# NUCLEO.net
KiCad netlist of a schematic drawn in Altium Designer
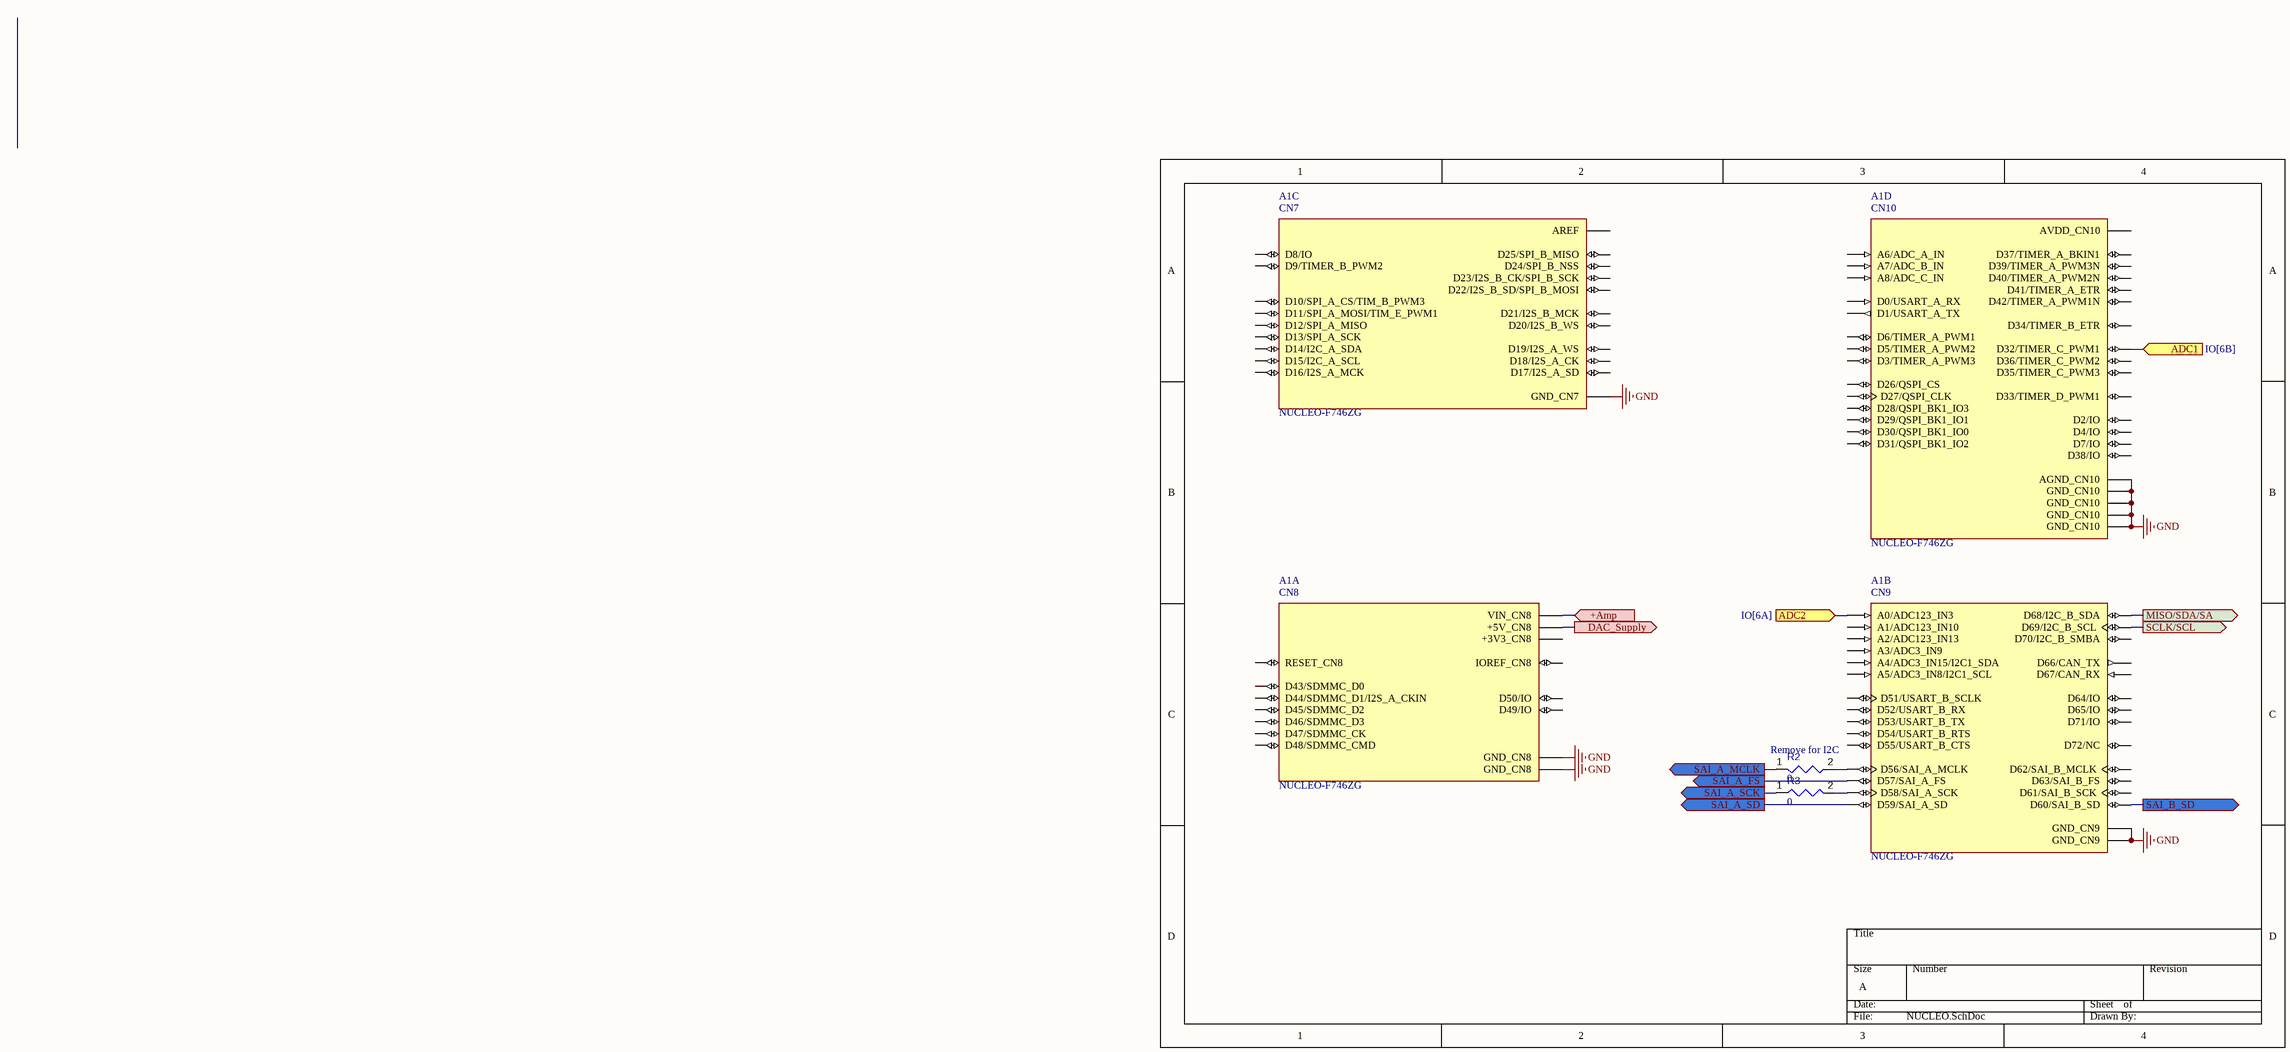
[diagram p0: NUCLEO.SchDoc]

(export (version "E")
  (design (tool "Eeschema 10.0.6"))
  (components
    (comp (ref "A1")
      (value "NUCLEO-F746ZG")
      (footprint "MODULE_NUCLEO-F746ZG")
      (fields (field (name "MF") "STMicroelectronics"))
      (libsource (lib "NUCLEO-F746ZG_NoOutline_InnerRow") (part "NUCLEO-F746ZG"))
    )
    (comp (ref "R2")
      (value "0")
      (footprint "RESC0603(1608)_L")
      (description "0Ohm 0603")
      (libsource (lib "Northeastern University") (part "RES-2"))
    )
    (comp (ref "R3")
      (value "0")
      (footprint "RESC0603(1608)_L")
      (description "0ohm 0603")
      (libsource (lib "Northeastern University") (part "RES-2"))
    )
  )
  (nets
    (net (code "1") (name "/+Amp") (class "Default")
      (node (ref "A1") (pin "CN8_15") (pinfunction "VIN_CN8_CN8_15") (pintype "power_in"))
    )
    (net (code "2") (name "/ADC1") (class "Default")
      (node (ref "A1") (pin "CN10_29") (pinfunction "D32/TIMER_C_PWM1_CN10_29") (pintype "bidirectional"))
    )
    (net (code "3") (name "/ADC2") (class "Default")
      (node (ref "A1") (pin "CN9_1") (pinfunction "A0/ADC123_IN3_CN9_1") (pintype "input"))
    )
    (net (code "4") (name "/DAC_Supply") (class "Default")
      (node (ref "A1") (pin "CN8_9") (pinfunction "+5V_CN8_CN8_9") (pintype "power_in"))
    )
    (net (code "5") (name "/MISO{slash}SDA{slash}SA") (class "Default")
      (node (ref "A1") (pin "CN9_21") (pinfunction "D68/I2C_B_SDA_CN9_21") (pintype "bidirectional"))
    )
    (net (code "6") (name "/SAI_A_FS") (class "Default")
      (node (ref "A1") (pin "CN9_16") (pinfunction "D57/SAI_A_FS_CN9_16") (pintype "bidirectional"))
    )
    (net (code "7") (name "/SAI_A_MCLK") (class "Default")
      (node (ref "R2") (pin "1") (pinfunction "1_1") (pintype "passive"))
    )
    (net (code "8") (name "/SAI_A_SCK") (class "Default")
      (node (ref "R3") (pin "1") (pinfunction "1_1") (pintype "passive"))
    )
    (net (code "9") (name "/SAI_A_SD") (class "Default")
      (node (ref "A1") (pin "CN9_20") (pinfunction "D59/SAI_A_SD_CN9_20") (pintype "bidirectional"))
    )
    (net (code "10") (name "/SAI_B_SD") (class "Default")
      (node (ref "A1") (pin "CN9_22") (pinfunction "D60/SAI_B_SD_CN9_22") (pintype "bidirectional"))
    )
    (net (code "11") (name "/SCLK{slash}SCL") (class "Default")
      (node (ref "A1") (pin "CN9_19") (pinfunction "D69/I2C_B_SCL_CN9_19") (pintype "bidirectional"))
    )
    (net (code "12") (name "GND") (class "Default")
      (node (ref "A1") (pin "CN10_17") (pinfunction "GND_CN10_CN10_17") (pintype "power_in"))
      (node (ref "A1") (pin "CN10_22") (pinfunction "GND_CN10_CN10_22") (pintype "power_in"))
      (node (ref "A1") (pin "CN10_27") (pinfunction "GND_CN10_CN10_27") (pintype "power_in"))
      (node (ref "A1") (pin "CN10_3") (pinfunction "AGND_CN10_CN10_3") (pintype "power_in"))
      (node (ref "A1") (pin "CN10_5") (pinfunction "GND_CN10_CN10_5") (pintype "power_in"))
      (node (ref "A1") (pin "CN7_8") (pinfunction "GND_CN7_CN7_8") (pintype "power_in"))
      (node (ref "A1") (pin "CN8_11") (pinfunction "GND_CN8_CN8_11") (pintype "power_in"))
      (node (ref "A1") (pin "CN8_13") (pinfunction "GND_CN8_CN8_13") (pintype "power_in"))
      (node (ref "A1") (pin "CN9_12") (pinfunction "GND_CN9_CN9_12") (pintype "power_in"))
      (node (ref "A1") (pin "CN9_23") (pinfunction "GND_CN9_CN9_23") (pintype "power_in"))
    )
    (net (code "13") (name "Net-(A1B-D56{slash}SAI_A_MCLK)") (class "Default")
      (node (ref "A1") (pin "CN9_14") (pinfunction "D56/SAI_A_MCLK_CN9_14") (pintype "bidirectional"))
      (node (ref "R2") (pin "2") (pinfunction "2_2") (pintype "passive"))
    )
    (net (code "14") (name "Net-(A1B-D58{slash}SAI_A_SCK)") (class "Default")
      (node (ref "A1") (pin "CN9_18") (pinfunction "D58/SAI_A_SCK_CN9_18") (pintype "bidirectional"))
      (node (ref "R3") (pin "2") (pinfunction "2_2") (pintype "passive"))
    )
    (net (code "15") (name "unconnected-(A1A-+3V3_CN8-PadCN8_7)") (class "Default")
      (node (ref "A1") (pin "CN8_7") (pinfunction "+3V3_CN8_CN8_7") (pintype "power_in"))
    )
    (net (code "16") (name "unconnected-(A1A-D43{slash}SDMMC_D0-PadCN8_2)") (class "Default")
      (node (ref "A1") (pin "CN8_2") (pinfunction "D43/SDMMC_D0_CN8_2") (pintype "bidirectional"))
    )
    (net (code "17") (name "unconnected-(A1A-D44{slash}SDMMC_D1{slash}I2S_A_CKIN-PadCN8_4)") (class "Default")
      (node (ref "A1") (pin "CN8_4") (pinfunction "D44/SDMMC_D1/I2S_A_CKIN_CN8_4") (pintype "bidirectional"))
    )
    (net (code "18") (name "unconnected-(A1A-D45{slash}SDMMC_D2-PadCN8_6)") (class "Default")
      (node (ref "A1") (pin "CN8_6") (pinfunction "D45/SDMMC_D2_CN8_6") (pintype "bidirectional"))
    )
    (net (code "19") (name "unconnected-(A1A-D46{slash}SDMMC_D3-PadCN8_8)") (class "Default")
      (node (ref "A1") (pin "CN8_8") (pinfunction "D46/SDMMC_D3_CN8_8") (pintype "bidirectional"))
    )
    (net (code "20") (name "unconnected-(A1A-D47{slash}SDMMC_CK-PadCN8_10)") (class "Default")
      (node (ref "A1") (pin "CN8_10") (pinfunction "D47/SDMMC_CK_CN8_10") (pintype "bidirectional"))
    )
    (net (code "21") (name "unconnected-(A1A-D48{slash}SDMMC_CMD-PadCN8_12)") (class "Default")
      (node (ref "A1") (pin "CN8_12") (pinfunction "D48/SDMMC_CMD_CN8_12") (pintype "bidirectional"))
    )
    (net (code "22") (name "unconnected-(A1A-D49{slash}IO-PadCN8_14)") (class "Default")
      (node (ref "A1") (pin "CN8_14") (pinfunction "D49/IO_CN8_14") (pintype "bidirectional"))
    )
    (net (code "23") (name "unconnected-(A1A-D50{slash}IO-PadCN8_16)") (class "Default")
      (node (ref "A1") (pin "CN8_16") (pinfunction "D50/IO_CN8_16") (pintype "bidirectional"))
    )
    (net (code "24") (name "unconnected-(A1A-IOREF_CN8-PadCN8_3)") (class "Default")
      (node (ref "A1") (pin "CN8_3") (pinfunction "IOREF_CN8_CN8_3") (pintype "bidirectional"))
    )
    (net (code "25") (name "unconnected-(A1A-RESET_CN8-PadCN8_5)") (class "Default")
      (node (ref "A1") (pin "CN8_5") (pinfunction "RESET_CN8_CN8_5") (pintype "bidirectional"))
    )
    (net (code "26") (name "unconnected-(A1B-A1{slash}ADC123_IN10-PadCN9_3)") (class "Default")
      (node (ref "A1") (pin "CN9_3") (pinfunction "A1/ADC123_IN10_CN9_3") (pintype "input"))
    )
    (net (code "27") (name "unconnected-(A1B-A2{slash}ADC123_IN13-PadCN9_5)") (class "Default")
      (node (ref "A1") (pin "CN9_5") (pinfunction "A2/ADC123_IN13_CN9_5") (pintype "input"))
    )
    (net (code "28") (name "unconnected-(A1B-A3{slash}ADC3_IN9-PadCN9_7)") (class "Default")
      (node (ref "A1") (pin "CN9_7") (pinfunction "A3/ADC3_IN9_CN9_7") (pintype "input"))
    )
    (net (code "29") (name "unconnected-(A1B-A4{slash}ADC3_IN15{slash}I2C1_SDA-PadCN9_9)") (class "Default")
      (node (ref "A1") (pin "CN9_9") (pinfunction "A4/ADC3_IN15/I2C1_SDA_CN9_9") (pintype "input"))
    )
    (net (code "30") (name "unconnected-(A1B-A5{slash}ADC3_IN8{slash}I2C1_SCL-PadCN9_11)") (class "Default")
      (node (ref "A1") (pin "CN9_11") (pinfunction "A5/ADC3_IN8/I2C1_SCL_CN9_11") (pintype "input"))
    )
    (net (code "31") (name "unconnected-(A1B-D51{slash}USART_B_SCLK-PadCN9_2)") (class "Default")
      (node (ref "A1") (pin "CN9_2") (pinfunction "D51/USART_B_SCLK_CN9_2") (pintype "bidirectional"))
    )
    (net (code "32") (name "unconnected-(A1B-D52{slash}USART_B_RX-PadCN9_4)") (class "Default")
      (node (ref "A1") (pin "CN9_4") (pinfunction "D52/USART_B_RX_CN9_4") (pintype "bidirectional"))
    )
    (net (code "33") (name "unconnected-(A1B-D53{slash}USART_B_TX-PadCN9_6)") (class "Default")
      (node (ref "A1") (pin "CN9_6") (pinfunction "D53/USART_B_TX_CN9_6") (pintype "bidirectional"))
    )
    (net (code "34") (name "unconnected-(A1B-D54{slash}USART_B_RTS-PadCN9_8)") (class "Default")
      (node (ref "A1") (pin "CN9_8") (pinfunction "D54/USART_B_RTS_CN9_8") (pintype "bidirectional"))
    )
    (net (code "35") (name "unconnected-(A1B-D55{slash}USART_B_CTS-PadCN9_10)") (class "Default")
      (node (ref "A1") (pin "CN9_10") (pinfunction "D55/USART_B_CTS_CN9_10") (pintype "bidirectional"))
    )
    (net (code "36") (name "unconnected-(A1B-D61{slash}SAI_B_SCK-PadCN9_24)") (class "Default")
      (node (ref "A1") (pin "CN9_24") (pinfunction "D61/SAI_B_SCK_CN9_24") (pintype "bidirectional"))
    )
    (net (code "37") (name "unconnected-(A1B-D62{slash}SAI_B_MCLK-PadCN9_26)") (class "Default")
      (node (ref "A1") (pin "CN9_26") (pinfunction "D62/SAI_B_MCLK_CN9_26") (pintype "bidirectional"))
    )
    (net (code "38") (name "unconnected-(A1B-D63{slash}SAI_B_FS-PadCN9_28)") (class "Default")
      (node (ref "A1") (pin "CN9_28") (pinfunction "D63/SAI_B_FS_CN9_28") (pintype "bidirectional"))
    )
    (net (code "39") (name "unconnected-(A1B-D64{slash}IO-PadCN9_30)") (class "Default")
      (node (ref "A1") (pin "CN9_30") (pinfunction "D64/IO_CN9_30") (pintype "bidirectional"))
    )
    (net (code "40") (name "unconnected-(A1B-D65{slash}IO-PadCN9_29)") (class "Default")
      (node (ref "A1") (pin "CN9_29") (pinfunction "D65/IO_CN9_29") (pintype "bidirectional"))
    )
    (net (code "41") (name "unconnected-(A1B-D66{slash}CAN_TX-PadCN9_27)") (class "Default")
      (node (ref "A1") (pin "CN9_27") (pinfunction "D66/CAN_TX_CN9_27") (pintype "output"))
    )
    (net (code "42") (name "unconnected-(A1B-D67{slash}CAN_RX-PadCN9_25)") (class "Default")
      (node (ref "A1") (pin "CN9_25") (pinfunction "D67/CAN_RX_CN9_25") (pintype "input"))
    )
    (net (code "43") (name "unconnected-(A1B-D70{slash}I2C_B_SMBA-PadCN9_17)") (class "Default")
      (node (ref "A1") (pin "CN9_17") (pinfunction "D70/I2C_B_SMBA_CN9_17") (pintype "bidirectional"))
    )
    (net (code "44") (name "unconnected-(A1B-D71{slash}IO-PadCN9_15)") (class "Default")
      (node (ref "A1") (pin "CN9_15") (pinfunction "D71/IO_CN9_15") (pintype "bidirectional"))
    )
    (net (code "45") (name "unconnected-(A1B-D72{slash}NC-PadCN9_13)") (class "Default")
      (node (ref "A1") (pin "CN9_13") (pinfunction "D72/NC_CN9_13") (pintype "bidirectional"))
    )
    (net (code "46") (name "unconnected-(A1C-AREF-PadCN7_6)") (class "Default")
      (node (ref "A1") (pin "CN7_6") (pinfunction "AREF_CN7_6") (pintype "power_in"))
    )
    (net (code "47") (name "unconnected-(A1C-D8{slash}IO-PadCN7_20)") (class "Default")
      (node (ref "A1") (pin "CN7_20") (pinfunction "D8/IO_CN7_20") (pintype "bidirectional"))
    )
    (net (code "48") (name "unconnected-(A1C-D9{slash}TIMER_B_PWM2-PadCN7_18)") (class "Default")
      (node (ref "A1") (pin "CN7_18") (pinfunction "D9/TIMER_B_PWM2_CN7_18") (pintype "bidirectional"))
    )
    (net (code "49") (name "unconnected-(A1C-D10{slash}SPI_A_CS{slash}TIM_B_PWM3-PadCN7_16)") (class "Default")
      (node (ref "A1") (pin "CN7_16") (pinfunction "D10/SPI_A_CS/TIM_B_PWM3_CN7_16") (pintype "bidirectional"))
    )
    (net (code "50") (name "unconnected-(A1C-D11{slash}SPI_A_MOSI{slash}TIM_E_PWM1-PadCN7_14)") (class "Default")
      (node (ref "A1") (pin "CN7_14") (pinfunction "D11/SPI_A_MOSI/TIM_E_PWM1_CN7_14") (pintype "bidirectional"))
    )
    (net (code "51") (name "unconnected-(A1C-D12{slash}SPI_A_MISO-PadCN7_12)") (class "Default")
      (node (ref "A1") (pin "CN7_12") (pinfunction "D12/SPI_A_MISO_CN7_12") (pintype "bidirectional"))
    )
    (net (code "52") (name "unconnected-(A1C-D13{slash}SPI_A_SCK-PadCN7_10)") (class "Default")
      (node (ref "A1") (pin "CN7_10") (pinfunction "D13/SPI_A_SCK_CN7_10") (pintype "bidirectional"))
    )
    (net (code "53") (name "unconnected-(A1C-D14{slash}I2C_A_SDA-PadCN7_4)") (class "Default")
      (node (ref "A1") (pin "CN7_4") (pinfunction "D14/I2C_A_SDA_CN7_4") (pintype "bidirectional"))
    )
    (net (code "54") (name "unconnected-(A1C-D15{slash}I2C_A_SCL-PadCN7_2)") (class "Default")
      (node (ref "A1") (pin "CN7_2") (pinfunction "D15/I2C_A_SCL_CN7_2") (pintype "bidirectional"))
    )
    (net (code "55") (name "unconnected-(A1C-D16{slash}I2S_A_MCK-PadCN7_1)") (class "Default")
      (node (ref "A1") (pin "CN7_1") (pinfunction "D16/I2S_A_MCK_CN7_1") (pintype "bidirectional"))
    )
    (net (code "56") (name "unconnected-(A1C-D17{slash}I2S_A_SD-PadCN7_3)") (class "Default")
      (node (ref "A1") (pin "CN7_3") (pinfunction "D17/I2S_A_SD_CN7_3") (pintype "bidirectional"))
    )
    (net (code "57") (name "unconnected-(A1C-D18{slash}I2S_A_CK-PadCN7_5)") (class "Default")
      (node (ref "A1") (pin "CN7_5") (pinfunction "D18/I2S_A_CK_CN7_5") (pintype "bidirectional"))
    )
    (net (code "58") (name "unconnected-(A1C-D19{slash}I2S_A_WS-PadCN7_7)") (class "Default")
      (node (ref "A1") (pin "CN7_7") (pinfunction "D19/I2S_A_WS_CN7_7") (pintype "bidirectional"))
    )
    (net (code "59") (name "unconnected-(A1C-D20{slash}I2S_B_WS-PadCN7_9)") (class "Default")
      (node (ref "A1") (pin "CN7_9") (pinfunction "D20/I2S_B_WS_CN7_9") (pintype "bidirectional"))
    )
    (net (code "60") (name "unconnected-(A1C-D21{slash}I2S_B_MCK-PadCN7_11)") (class "Default")
      (node (ref "A1") (pin "CN7_11") (pinfunction "D21/I2S_B_MCK_CN7_11") (pintype "bidirectional"))
    )
    (net (code "61") (name "unconnected-(A1C-D22{slash}I2S_B_SD{slash}SPI_B_MOSI-PadCN7_13)") (class "Default")
      (node (ref "A1") (pin "CN7_13") (pinfunction "D22/I2S_B_SD/SPI_B_MOSI_CN7_13") (pintype "bidirectional"))
    )
    (net (code "62") (name "unconnected-(A1C-D23{slash}I2S_B_CK{slash}SPI_B_SCK-PadCN7_15)") (class "Default")
      (node (ref "A1") (pin "CN7_15") (pinfunction "D23/I2S_B_CK/SPI_B_SCK_CN7_15") (pintype "bidirectional"))
    )
    (net (code "63") (name "unconnected-(A1C-D24{slash}SPI_B_NSS-PadCN7_17)") (class "Default")
      (node (ref "A1") (pin "CN7_17") (pinfunction "D24/SPI_B_NSS_CN7_17") (pintype "bidirectional"))
    )
    (net (code "64") (name "unconnected-(A1C-D25{slash}SPI_B_MISO-PadCN7_19)") (class "Default")
      (node (ref "A1") (pin "CN7_19") (pinfunction "D25/SPI_B_MISO_CN7_19") (pintype "bidirectional"))
    )
    (net (code "65") (name "unconnected-(A1D-A6{slash}ADC_A_IN-PadCN10_7)") (class "Default")
      (node (ref "A1") (pin "CN10_7") (pinfunction "A6/ADC_A_IN_CN10_7") (pintype "input"))
    )
    (net (code "66") (name "unconnected-(A1D-A7{slash}ADC_B_IN-PadCN10_9)") (class "Default")
      (node (ref "A1") (pin "CN10_9") (pinfunction "A7/ADC_B_IN_CN10_9") (pintype "input"))
    )
    (net (code "67") (name "unconnected-(A1D-A8{slash}ADC_C_IN-PadCN10_11)") (class "Default")
      (node (ref "A1") (pin "CN10_11") (pinfunction "A8/ADC_C_IN_CN10_11") (pintype "input"))
    )
    (net (code "68") (name "unconnected-(A1D-AVDD_CN10-PadCN10_1)") (class "Default")
      (node (ref "A1") (pin "CN10_1") (pinfunction "AVDD_CN10_CN10_1") (pintype "power_in"))
    )
    (net (code "69") (name "unconnected-(A1D-D0{slash}USART_A_RX-PadCN10_16)") (class "Default")
      (node (ref "A1") (pin "CN10_16") (pinfunction "D0/USART_A_RX_CN10_16") (pintype "input"))
    )
    (net (code "70") (name "unconnected-(A1D-D1{slash}USART_A_TX-PadCN10_14)") (class "Default")
      (node (ref "A1") (pin "CN10_14") (pinfunction "D1/USART_A_TX_CN10_14") (pintype "output"))
    )
    (net (code "71") (name "unconnected-(A1D-D2{slash}IO-PadCN10_12)") (class "Default")
      (node (ref "A1") (pin "CN10_12") (pinfunction "D2/IO_CN10_12") (pintype "bidirectional"))
    )
    (net (code "72") (name "unconnected-(A1D-D3{slash}TIMER_A_PWM3-PadCN10_10)") (class "Default")
      (node (ref "A1") (pin "CN10_10") (pinfunction "D3/TIMER_A_PWM3_CN10_10") (pintype "bidirectional"))
    )
    (net (code "73") (name "unconnected-(A1D-D4{slash}IO-PadCN10_8)") (class "Default")
      (node (ref "A1") (pin "CN10_8") (pinfunction "D4/IO_CN10_8") (pintype "bidirectional"))
    )
    (net (code "74") (name "unconnected-(A1D-D5{slash}TIMER_A_PWM2-PadCN10_6)") (class "Default")
      (node (ref "A1") (pin "CN10_6") (pinfunction "D5/TIMER_A_PWM2_CN10_6") (pintype "bidirectional"))
    )
    (net (code "75") (name "unconnected-(A1D-D6{slash}TIMER_A_PWM1-PadCN10_4)") (class "Default")
      (node (ref "A1") (pin "CN10_4") (pinfunction "D6/TIMER_A_PWM1_CN10_4") (pintype "bidirectional"))
    )
    (net (code "76") (name "unconnected-(A1D-D7{slash}IO-PadCN10_2)") (class "Default")
      (node (ref "A1") (pin "CN10_2") (pinfunction "D7/IO_CN10_2") (pintype "bidirectional"))
    )
    (net (code "77") (name "unconnected-(A1D-D26{slash}QSPI_CS-PadCN10_13)") (class "Default")
      (node (ref "A1") (pin "CN10_13") (pinfunction "D26/QSPI_CS_CN10_13") (pintype "bidirectional"))
    )
    (net (code "78") (name "unconnected-(A1D-D27{slash}QSPI_CLK-PadCN10_15)") (class "Default")
      (node (ref "A1") (pin "CN10_15") (pinfunction "D27/QSPI_CLK_CN10_15") (pintype "bidirectional"))
    )
    (net (code "79") (name "unconnected-(A1D-D28{slash}QSPI_BK1_IO3-PadCN10_19)") (class "Default")
      (node (ref "A1") (pin "CN10_19") (pinfunction "D28/QSPI_BK1_IO3_CN10_19") (pintype "bidirectional"))
    )
    (net (code "80") (name "unconnected-(A1D-D29{slash}QSPI_BK1_IO1-PadCN10_21)") (class "Default")
      (node (ref "A1") (pin "CN10_21") (pinfunction "D29/QSPI_BK1_IO1_CN10_21") (pintype "bidirectional"))
    )
    (net (code "81") (name "unconnected-(A1D-D30{slash}QSPI_BK1_IO0-PadCN10_23)") (class "Default")
      (node (ref "A1") (pin "CN10_23") (pinfunction "D30/QSPI_BK1_IO0_CN10_23") (pintype "bidirectional"))
    )
    (net (code "82") (name "unconnected-(A1D-D31{slash}QSPI_BK1_IO2-PadCN10_25)") (class "Default")
      (node (ref "A1") (pin "CN10_25") (pinfunction "D31/QSPI_BK1_IO2_CN10_25") (pintype "bidirectional"))
    )
    (net (code "83") (name "unconnected-(A1D-D33{slash}TIMER_D_PWM1-PadCN10_31)") (class "Default")
      (node (ref "A1") (pin "CN10_31") (pinfunction "D33/TIMER_D_PWM1_CN10_31") (pintype "bidirectional"))
    )
    (net (code "84") (name "unconnected-(A1D-D34{slash}TIMER_B_ETR-PadCN10_33)") (class "Default")
      (node (ref "A1") (pin "CN10_33") (pinfunction "D34/TIMER_B_ETR_CN10_33") (pintype "bidirectional"))
    )
    (net (code "85") (name "unconnected-(A1D-D35{slash}TIMER_C_PWM3-PadCN10_34)") (class "Default")
      (node (ref "A1") (pin "CN10_34") (pinfunction "D35/TIMER_C_PWM3_CN10_34") (pintype "bidirectional"))
    )
    (net (code "86") (name "unconnected-(A1D-D36{slash}TIMER_C_PWM2-PadCN10_32)") (class "Default")
      (node (ref "A1") (pin "CN10_32") (pinfunction "D36/TIMER_C_PWM2_CN10_32") (pintype "bidirectional"))
    )
    (net (code "87") (name "unconnected-(A1D-D37{slash}TIMER_A_BKIN1-PadCN10_30)") (class "Default")
      (node (ref "A1") (pin "CN10_30") (pinfunction "D37/TIMER_A_BKIN1_CN10_30") (pintype "bidirectional"))
    )
    (net (code "88") (name "unconnected-(A1D-D38{slash}IO-PadCN10_28)") (class "Default")
      (node (ref "A1") (pin "CN10_28") (pinfunction "D38/IO_CN10_28") (pintype "bidirectional"))
    )
    (net (code "89") (name "unconnected-(A1D-D39{slash}TIMER_A_PWM3N-PadCN10_26)") (class "Default")
      (node (ref "A1") (pin "CN10_26") (pinfunction "D39/TIMER_A_PWM3N_CN10_26") (pintype "bidirectional"))
    )
    (net (code "90") (name "unconnected-(A1D-D40{slash}TIMER_A_PWM2N-PadCN10_24)") (class "Default")
      (node (ref "A1") (pin "CN10_24") (pinfunction "D40/TIMER_A_PWM2N_CN10_24") (pintype "bidirectional"))
    )
    (net (code "91") (name "unconnected-(A1D-D41{slash}TIMER_A_ETR-PadCN10_20)") (class "Default")
      (node (ref "A1") (pin "CN10_20") (pinfunction "D41/TIMER_A_ETR_CN10_20") (pintype "bidirectional"))
    )
    (net (code "92") (name "unconnected-(A1D-D42{slash}TIMER_A_PWM1N-PadCN10_18)") (class "Default")
      (node (ref "A1") (pin "CN10_18") (pinfunction "D42/TIMER_A_PWM1N_CN10_18") (pintype "bidirectional"))
    )
  )
)
